# FAN.net
KiCad netlist of a schematic drawn in EAGLE
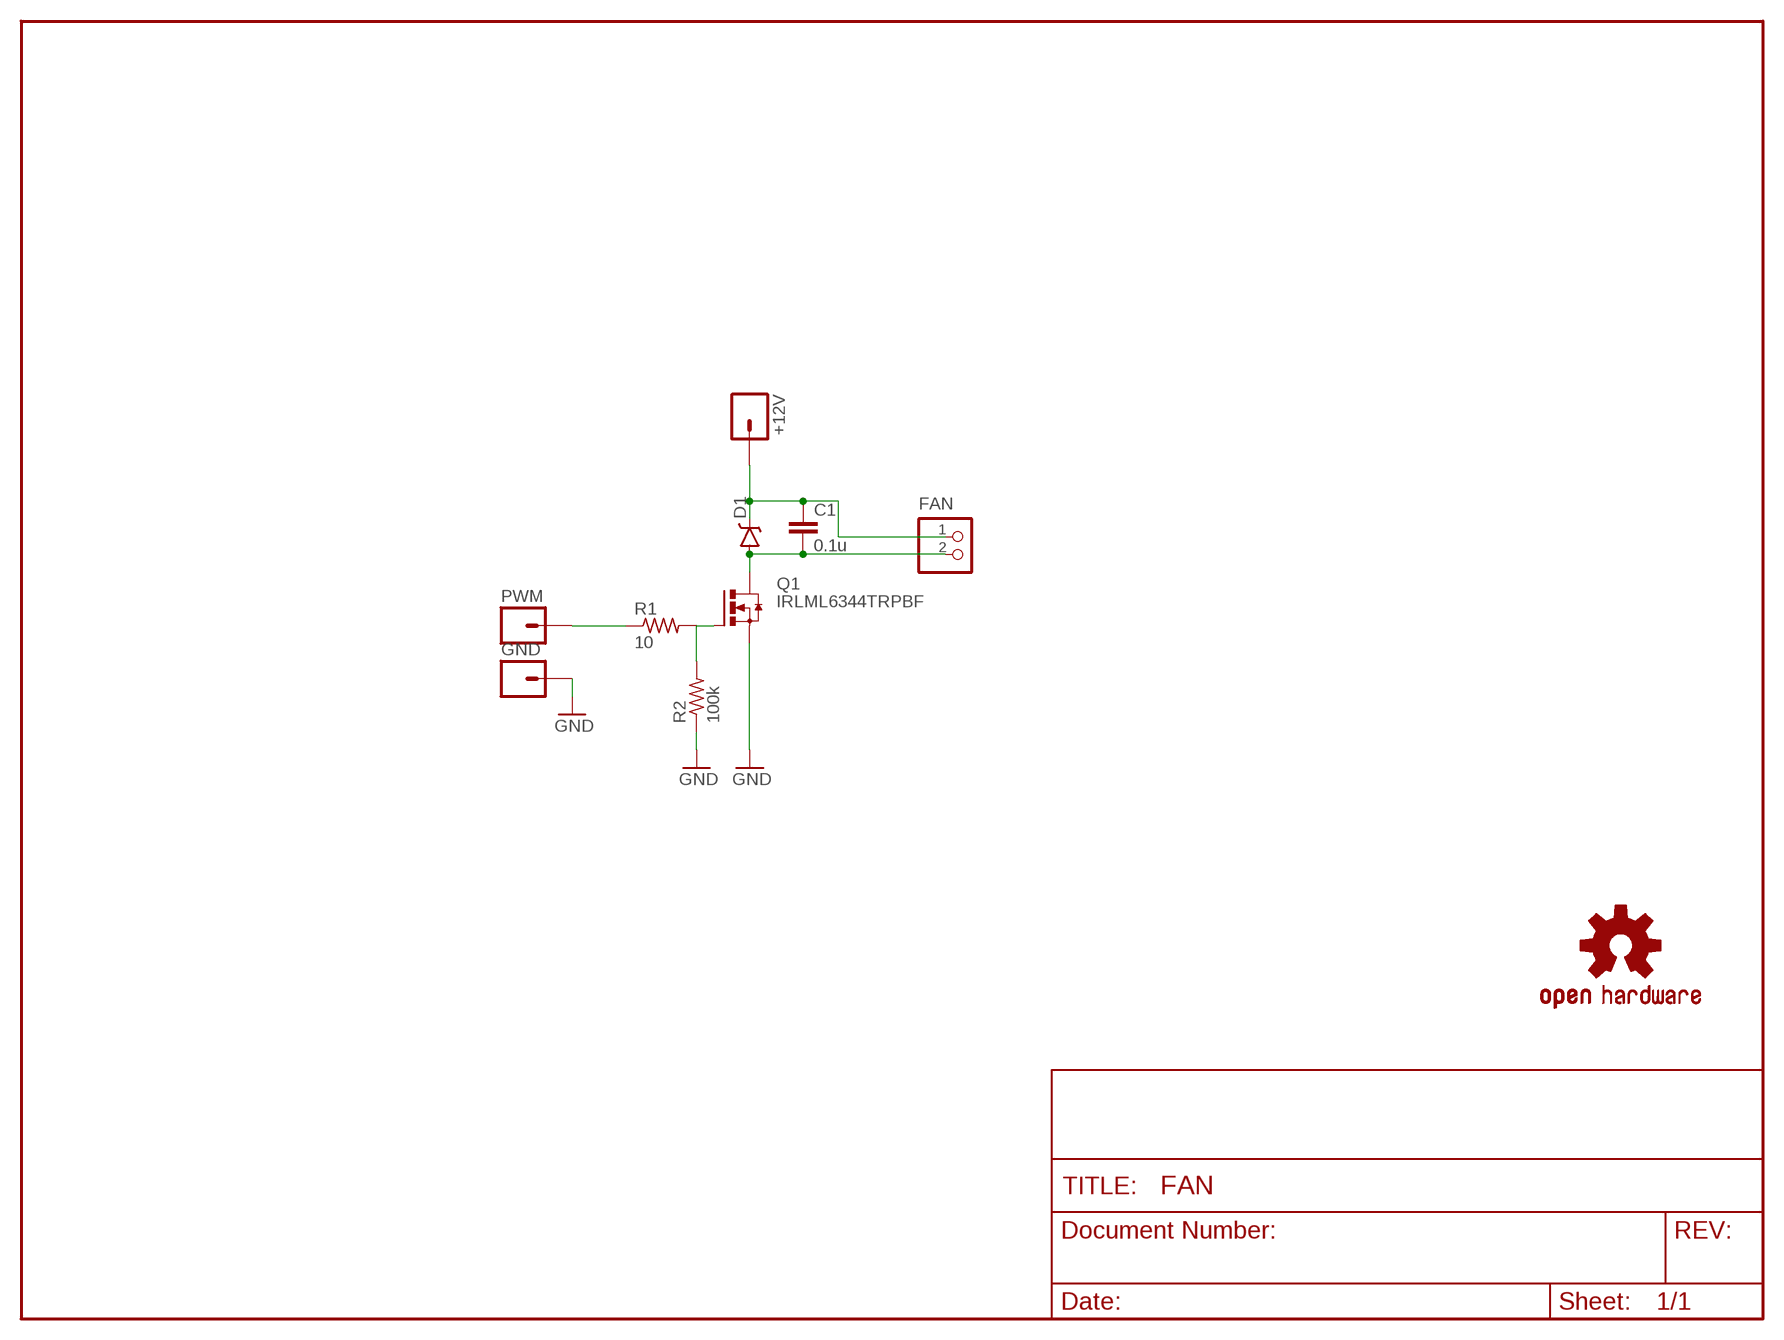
[diagram p0: schematic, sheet 1]

(export (version "E")
  (design (tool "Eeschema 10.0.6"))
  (components
    (comp (ref "+12V")
      (value "M01PTH")
      (footprint "eagle-import:1X01")
      (libsource (lib "eagle-import") (part "M01PTH"))
    )
    (comp (ref "C1")
      (value "0.1u")
      (footprint "eagle-import:0603-CAP")
      (libsource (lib "eagle-import") (part "CAP0603-CAP"))
    )
    (comp (ref "D1")
      (value "DIODE-SCHOTTKY")
      (footprint "eagle-import:TUMD2")
      (libsource (lib "eagle-import") (part "DIODE-SCHOTTKY"))
    )
    (comp (ref "FAN")
      (value "S2B-XH-A")
      (footprint "eagle-import:S2B-XH-A")
      (libsource (lib "eagle-import") (part "S2B-XH-A"))
    )
    (comp (ref "GND")
      (value "M01PTH")
      (footprint "eagle-import:1X01")
      (libsource (lib "eagle-import") (part "M01PTH"))
    )
    (comp (ref "PWM")
      (value "M01PTH")
      (footprint "eagle-import:1X01")
      (libsource (lib "eagle-import") (part "M01PTH"))
    )
    (comp (ref "Q1")
      (value "IRLML6344TRPBF")
      (footprint "eagle-import:SOT-23-3")
      (fields (field (name "MANUFACTURER") "International Rectifier"))
      (libsource (lib "eagle-import") (part "IRLML6344TRPBF"))
    )
    (comp (ref "R1")
      (value "10")
      (footprint "eagle-import:1608")
      (libsource (lib "eagle-import") (part "R-US_1608"))
    )
    (comp (ref "R2")
      (value "100k")
      (footprint "eagle-import:1608")
      (libsource (lib "eagle-import") (part "R-US_1608"))
    )
    (comp (ref "U$1")
      (value "OSHW-LOGOS")
      (footprint "eagle-import:OSHW-LOGO-S")
      (libsource (lib "eagle-import") (part "OSHW-LOGOS"))
    )
  )
  (nets
    (net (code "1") (name "GND") (class "Default")
      (node (ref "GND") (pin "1") (pinfunction "1_1") (pintype "passive"))
      (node (ref "Q1") (pin "2") (pinfunction "S_2") (pintype "passive"))
      (node (ref "R2") (pin "P$1") (pinfunction "1_P$1") (pintype "passive"))
    )
    (net (code "2") (name "Net-(+12V-Pad1)") (class "Default")
      (node (ref "+12V") (pin "1") (pinfunction "1_1") (pintype "passive"))
      (node (ref "C1") (pin "1") (pinfunction "1_1") (pintype "passive"))
      (node (ref "D1") (pin "C") (pinfunction "C_C") (pintype "passive"))
      (node (ref "FAN") (pin "1") (pinfunction "1_1") (pintype "passive"))
    )
    (net (code "3") (name "Net-(Q1-D)") (class "Default")
      (node (ref "C1") (pin "2") (pinfunction "2_2") (pintype "passive"))
      (node (ref "D1") (pin "A") (pinfunction "A_A") (pintype "passive"))
      (node (ref "FAN") (pin "2") (pinfunction "2_2") (pintype "passive"))
      (node (ref "Q1") (pin "3") (pinfunction "D_3") (pintype "passive"))
    )
    (net (code "4") (name "Net-(Q1-G)") (class "Default")
      (node (ref "Q1") (pin "1") (pinfunction "G_1") (pintype "passive"))
      (node (ref "R1") (pin "P$2") (pinfunction "2_P$2") (pintype "passive"))
      (node (ref "R2") (pin "P$2") (pinfunction "2_P$2") (pintype "passive"))
    )
    (net (code "5") (name "Net-(R1-1)") (class "Default")
      (node (ref "PWM") (pin "1") (pinfunction "1_1") (pintype "passive"))
      (node (ref "R1") (pin "P$1") (pinfunction "1_P$1") (pintype "passive"))
    )
  )
)
